# Model55.net
KiCad netlist of a schematic drawn in EAGLE
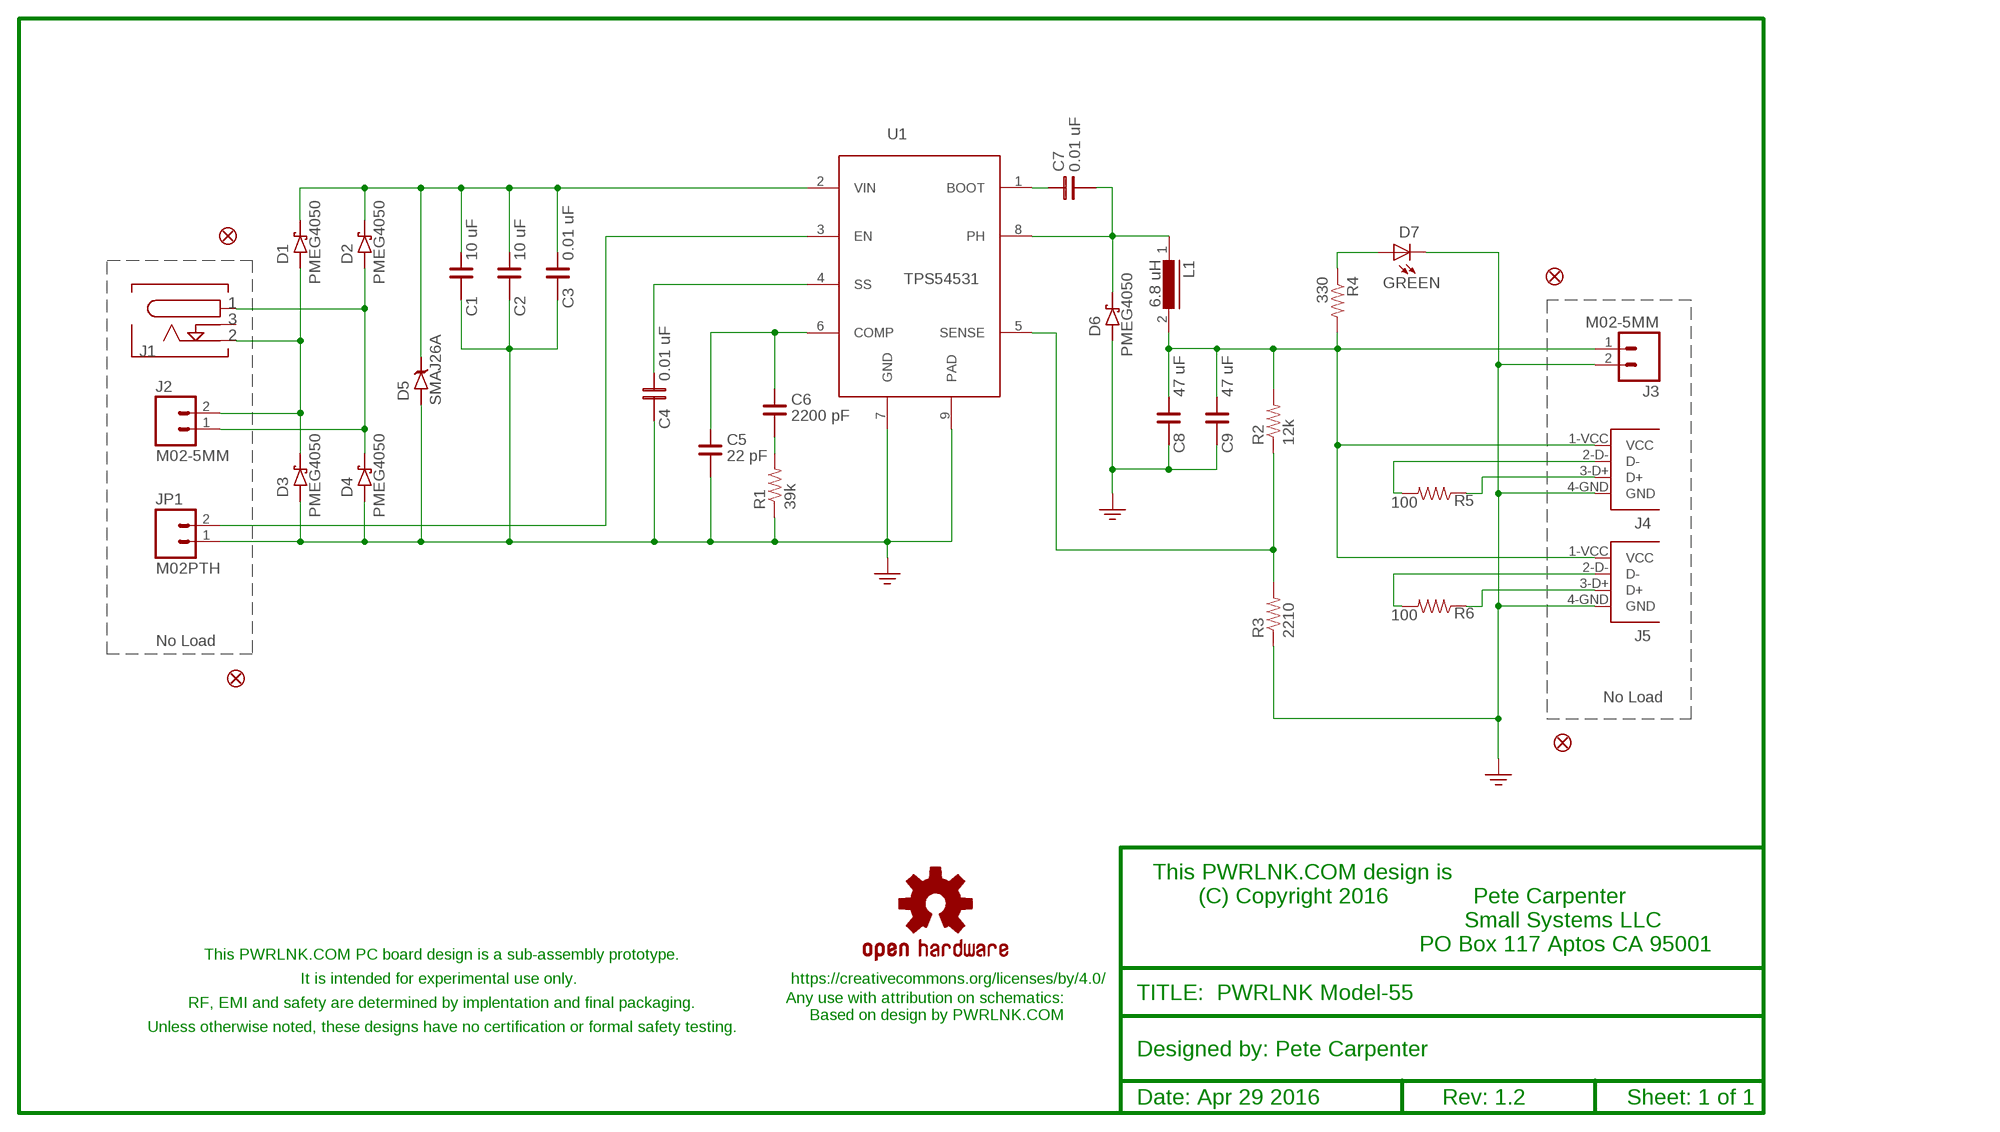
[diagram p0: schematic, sheet 1]

(export (version "E")
  (design (tool "Eeschema 10.0.6"))
  (components
    (comp (ref "C1")
      (value "10 uF")
      (footprint "eagle-import:1210")
      (libsource (lib "eagle-import") (part "CN-1210"))
    )
    (comp (ref "C2")
      (value "10 uF")
      (footprint "eagle-import:1210")
      (libsource (lib "eagle-import") (part "CN-1210"))
    )
    (comp (ref "C3")
      (value "0.01 uF")
      (footprint "eagle-import:0805")
      (libsource (lib "eagle-import") (part "CN-0805"))
    )
    (comp (ref "C4")
      (value "0.01 uF")
      (footprint "eagle-import:0805")
      (libsource (lib "eagle-import") (part "CN-0805"))
    )
    (comp (ref "C5")
      (value "22 pF")
      (footprint "eagle-import:0603")
      (libsource (lib "eagle-import") (part "CN-0603"))
    )
    (comp (ref "C6")
      (value "2200 pF")
      (footprint "eagle-import:0805")
      (libsource (lib "eagle-import") (part "CN-0805"))
    )
    (comp (ref "C7")
      (value "0.01 uF")
      (footprint "eagle-import:0805")
      (libsource (lib "eagle-import") (part "CN-0805"))
    )
    (comp (ref "C8")
      (value "47 uF")
      (footprint "eagle-import:C1206")
      (libsource (lib "eagle-import") (part "CN-1206"))
    )
    (comp (ref "C9")
      (value "47 uF")
      (footprint "eagle-import:C1206")
      (libsource (lib "eagle-import") (part "CN-1206"))
    )
    (comp (ref "D1")
      (value "PMEG4050EP")
      (footprint "eagle-import:SOD128")
      (libsource (lib "eagle-import") (part "PMEG4050EP"))
    )
    (comp (ref "D2")
      (value "PMEG4050EP")
      (footprint "eagle-import:SOD128")
      (libsource (lib "eagle-import") (part "PMEG4050EP"))
    )
    (comp (ref "D3")
      (value "PMEG4050EP")
      (footprint "eagle-import:SOD128")
      (libsource (lib "eagle-import") (part "PMEG4050EP"))
    )
    (comp (ref "D4")
      (value "PMEG4050EP")
      (footprint "eagle-import:SOD128")
      (libsource (lib "eagle-import") (part "PMEG4050EP"))
    )
    (comp (ref "D5")
      (value "SMAJ26A")
      (footprint "eagle-import:DO214BA")
      (libsource (lib "eagle-import") (part "SMAJ26A"))
    )
    (comp (ref "D6")
      (value "PMEG4050EP")
      (footprint "eagle-import:SOD128")
      (libsource (lib "eagle-import") (part "PMEG4050EP"))
    )
    (comp (ref "D7")
      (value "GREEN")
      (footprint "eagle-import:LED-0603")
      (libsource (lib "eagle-import") (part "LED-RED0603"))
    )
    (comp (ref "FID1")
      (value "FIDUCIAL1X2")
      (footprint "eagle-import:FIDUCIAL-1X2")
      (libsource (lib "eagle-import") (part "FIDUCIAL1X2"))
    )
    (comp (ref "FID2")
      (value "FIDUCIAL1X2")
      (footprint "eagle-import:FIDUCIAL-1X2")
      (libsource (lib "eagle-import") (part "FIDUCIAL1X2"))
    )
    (comp (ref "FID3")
      (value "FIDUCIAL1X2")
      (footprint "eagle-import:FIDUCIAL-1X2")
      (libsource (lib "eagle-import") (part "FIDUCIAL1X2"))
    )
    (comp (ref "FID4")
      (value "FIDUCIAL1X2")
      (footprint "eagle-import:FIDUCIAL-1X2")
      (libsource (lib "eagle-import") (part "FIDUCIAL1X2"))
    )
    (comp (ref "J1")
      (value "PJ-102AH")
      (footprint "eagle-import:PJ-102AH")
      (libsource (lib "eagle-import") (part "PJ-102AH"))
    )
    (comp (ref "J2")
      (value "M02-5MM")
      (footprint "eagle-import:SCREWTERMINAL-5MM-2")
      (libsource (lib "eagle-import") (part "M02-5MM"))
    )
    (comp (ref "J3")
      (value "M02-5MM")
      (footprint "eagle-import:SCREWTERMINAL-5MM-2")
      (libsource (lib "eagle-import") (part "M02-5MM"))
    )
    (comp (ref "J4")
      (value "87520")
      (footprint "eagle-import:87520-USB-A-FEMALE")
      (libsource (lib "eagle-import") (part "87520-USB-A-FEMALE"))
    )
    (comp (ref "J5")
      (value "87520")
      (footprint "eagle-import:87520-USB-A-FEMALE")
      (libsource (lib "eagle-import") (part "87520-USB-A-FEMALE"))
    )
    (comp (ref "JP1")
      (value "M02PTH")
      (footprint "eagle-import:1X02")
      (libsource (lib "eagle-import") (part "M02PTH"))
    )
    (comp (ref "L1")
      (value "6.8 uH")
      (footprint "eagle-import:DR125")
      (libsource (lib "eagle-import") (part "DR125"))
    )
    (comp (ref "LOGO1")
      (value "OSHW-LOGOL")
      (footprint "eagle-import:OSHW-LOGO-L")
      (libsource (lib "eagle-import") (part "OSHW-LOGOL"))
    )
    (comp (ref "R1")
      (value "39k")
      (footprint "eagle-import:0603-RES")
      (libsource (lib "eagle-import") (part "47KOHM1/10W1%(0603)"))
    )
    (comp (ref "R2")
      (value "12k")
      (footprint "eagle-import:0603-RES")
      (libsource (lib "eagle-import") (part "47KOHM1/10W1%(0603)"))
    )
    (comp (ref "R3")
      (value "2210")
      (footprint "eagle-import:0603-RES")
      (libsource (lib "eagle-import") (part "47KOHM1/10W1%(0603)"))
    )
    (comp (ref "R4")
      (value "330")
      (footprint "eagle-import:0603-RES")
      (libsource (lib "eagle-import") (part "47KOHM1/10W1%(0603)"))
    )
    (comp (ref "R5")
      (value "100")
      (footprint "eagle-import:0603-RES")
      (libsource (lib "eagle-import") (part "47KOHM1/10W1%(0603)"))
    )
    (comp (ref "R6")
      (value "100")
      (footprint "eagle-import:0603-RES")
      (libsource (lib "eagle-import") (part "47KOHM1/10W1%(0603)"))
    )
    (comp (ref "U1")
      (value "TPS54531")
      (footprint "eagle-import:SOIC127P600X170-9N")
      (libsource (lib "eagle-import") (part "TPS54531"))
    )
  )
  (nets
    (net (code "1") (name "GND") (class "Default")
      (node (ref "C1") (pin "2") (pinfunction "P$2_2") (pintype "bidirectional"))
      (node (ref "C2") (pin "2") (pinfunction "P$2_2") (pintype "bidirectional"))
      (node (ref "C3") (pin "2") (pinfunction "P$2_2") (pintype "bidirectional"))
      (node (ref "C4") (pin "2") (pinfunction "P$2_2") (pintype "bidirectional"))
      (node (ref "C5") (pin "2") (pinfunction "P$2_2") (pintype "bidirectional"))
      (node (ref "C8") (pin "2") (pinfunction "P$2_2") (pintype "bidirectional"))
      (node (ref "C9") (pin "2") (pinfunction "P$2_2") (pintype "bidirectional"))
      (node (ref "D3") (pin "P$1A") (pinfunction "P$1A_P$1A") (pintype "input"))
      (node (ref "D4") (pin "P$1A") (pinfunction "P$1A_P$1A") (pintype "input"))
      (node (ref "D5") (pin "A") (pinfunction "P$1A_A") (pintype "input"))
      (node (ref "D6") (pin "P$1A") (pinfunction "P$1A_P$1A") (pintype "input"))
      (node (ref "D7") (pin "C") (pinfunction "C_C") (pintype "passive"))
      (node (ref "J3") (pin "2") (pinfunction "2_2") (pintype "passive"))
      (node (ref "J4") (pin "4-GND") (pinfunction "GND_4-GND") (pintype "power_in"))
      (node (ref "J5") (pin "4-GND") (pinfunction "GND_4-GND") (pintype "power_in"))
      (node (ref "JP1") (pin "1") (pinfunction "1_1") (pintype "passive"))
      (node (ref "R1") (pin "1") (pinfunction "1_1") (pintype "passive"))
      (node (ref "R3") (pin "1") (pinfunction "1_1") (pintype "passive"))
      (node (ref "U1") (pin "7") (pinfunction "GND_7") (pintype "power_in"))
      (node (ref "U1") (pin "9") (pinfunction "PAD_9") (pintype "power_in"))
    )
    (net (code "2") (name "Net-(C1-P$1)") (class "Default")
      (node (ref "C1") (pin "1") (pinfunction "P$1_1") (pintype "bidirectional"))
      (node (ref "C2") (pin "1") (pinfunction "P$1_1") (pintype "bidirectional"))
      (node (ref "C3") (pin "1") (pinfunction "P$1_1") (pintype "bidirectional"))
      (node (ref "D1") (pin "P$2C") (pinfunction "P$2C_P$2C") (pintype "output"))
      (node (ref "D2") (pin "P$2C") (pinfunction "P$2C_P$2C") (pintype "output"))
      (node (ref "D5") (pin "C") (pinfunction "P$2C_C") (pintype "output"))
      (node (ref "U1") (pin "2") (pinfunction "VIN_2") (pintype "power_in"))
    )
    (net (code "3") (name "Net-(C4-P$1)") (class "Default")
      (node (ref "C4") (pin "1") (pinfunction "P$1_1") (pintype "bidirectional"))
      (node (ref "U1") (pin "4") (pinfunction "SS_4") (pintype "bidirectional"))
    )
    (net (code "4") (name "Net-(C5-P$1)") (class "Default")
      (node (ref "C5") (pin "1") (pinfunction "P$1_1") (pintype "bidirectional"))
      (node (ref "C6") (pin "1") (pinfunction "P$1_1") (pintype "bidirectional"))
      (node (ref "U1") (pin "6") (pinfunction "COMP_6") (pintype "bidirectional"))
    )
    (net (code "5") (name "Net-(C6-P$2)") (class "Default")
      (node (ref "C6") (pin "2") (pinfunction "P$2_2") (pintype "bidirectional"))
      (node (ref "R1") (pin "2") (pinfunction "2_2") (pintype "passive"))
    )
    (net (code "6") (name "Net-(C7-P$1)") (class "Default")
      (node (ref "C7") (pin "1") (pinfunction "P$1_1") (pintype "bidirectional"))
      (node (ref "U1") (pin "1") (pinfunction "BOOT_1") (pintype "input"))
    )
    (net (code "7") (name "Net-(C7-P$2)") (class "Default")
      (node (ref "C7") (pin "2") (pinfunction "P$2_2") (pintype "bidirectional"))
      (node (ref "D6") (pin "P$2C") (pinfunction "P$2C_P$2C") (pintype "output"))
      (node (ref "L1") (pin "1") (pinfunction "1_1") (pintype "passive"))
      (node (ref "U1") (pin "8") (pinfunction "PH_8") (pintype "power_in"))
    )
    (net (code "8") (name "Net-(C8-P$1)") (class "Default")
      (node (ref "C8") (pin "1") (pinfunction "P$1_1") (pintype "bidirectional"))
      (node (ref "C9") (pin "1") (pinfunction "P$1_1") (pintype "bidirectional"))
      (node (ref "J3") (pin "1") (pinfunction "1_1") (pintype "passive"))
      (node (ref "J4") (pin "1-VCC") (pinfunction "VCC_1-VCC") (pintype "power_in"))
      (node (ref "J5") (pin "1-VCC") (pinfunction "VCC_1-VCC") (pintype "power_in"))
      (node (ref "L1") (pin "2") (pinfunction "2_2") (pintype "passive"))
      (node (ref "R2") (pin "2") (pinfunction "2_2") (pintype "passive"))
      (node (ref "R4") (pin "2") (pinfunction "2_2") (pintype "passive"))
    )
    (net (code "9") (name "Net-(D7-PadA)") (class "Default")
      (node (ref "D7") (pin "A") (pinfunction "A_A") (pintype "passive"))
      (node (ref "R4") (pin "1") (pinfunction "1_1") (pintype "passive"))
    )
    (net (code "10") (name "Net-(J1-1)") (class "Default")
      (node (ref "D2") (pin "P$1A") (pinfunction "P$1A_P$1A") (pintype "input"))
      (node (ref "D4") (pin "P$2C") (pinfunction "P$2C_P$2C") (pintype "output"))
      (node (ref "J1") (pin "P$1") (pinfunction "1_P$1") (pintype "power_in"))
      (node (ref "J2") (pin "1") (pinfunction "1_1") (pintype "passive"))
    )
    (net (code "11") (name "Net-(J1-2)") (class "Default")
      (node (ref "D1") (pin "P$1A") (pinfunction "P$1A_P$1A") (pintype "input"))
      (node (ref "D3") (pin "P$2C") (pinfunction "P$2C_P$2C") (pintype "output"))
      (node (ref "J1") (pin "P$2") (pinfunction "2_P$2") (pintype "power_in"))
      (node (ref "J2") (pin "2") (pinfunction "2_2") (pintype "passive"))
    )
    (net (code "12") (name "Net-(J4-D+)") (class "Default")
      (node (ref "J4") (pin "3-D+") (pinfunction "D+_3-D+") (pintype "bidirectional"))
      (node (ref "R5") (pin "1") (pinfunction "1_1") (pintype "passive"))
    )
    (net (code "13") (name "Net-(J4-D-)") (class "Default")
      (node (ref "J4") (pin "2-D-") (pinfunction "D-_2-D-") (pintype "bidirectional"))
      (node (ref "R5") (pin "2") (pinfunction "2_2") (pintype "passive"))
    )
    (net (code "14") (name "Net-(J5-D+)") (class "Default")
      (node (ref "J5") (pin "3-D+") (pinfunction "D+_3-D+") (pintype "bidirectional"))
      (node (ref "R6") (pin "1") (pinfunction "1_1") (pintype "passive"))
    )
    (net (code "15") (name "Net-(J5-D-)") (class "Default")
      (node (ref "J5") (pin "2-D-") (pinfunction "D-_2-D-") (pintype "bidirectional"))
      (node (ref "R6") (pin "2") (pinfunction "2_2") (pintype "passive"))
    )
    (net (code "16") (name "Net-(U1-EN)") (class "Default")
      (node (ref "JP1") (pin "2") (pinfunction "2_2") (pintype "passive"))
      (node (ref "U1") (pin "3") (pinfunction "EN_3") (pintype "input"))
    )
    (net (code "17") (name "Net-(U1-SENSE)") (class "Default")
      (node (ref "R2") (pin "1") (pinfunction "1_1") (pintype "passive"))
      (node (ref "R3") (pin "2") (pinfunction "2_2") (pintype "passive"))
      (node (ref "U1") (pin "5") (pinfunction "SENSE_5") (pintype "bidirectional"))
    )
    (net (code "18") (name "unconnected-(J1-3-PadP$3)") (class "Default")
      (node (ref "J1") (pin "P$3") (pinfunction "3_P$3") (pintype "no_connect"))
    )
  )
)
